# main.net
KiCad netlist of a schematic drawn in Altium Designer
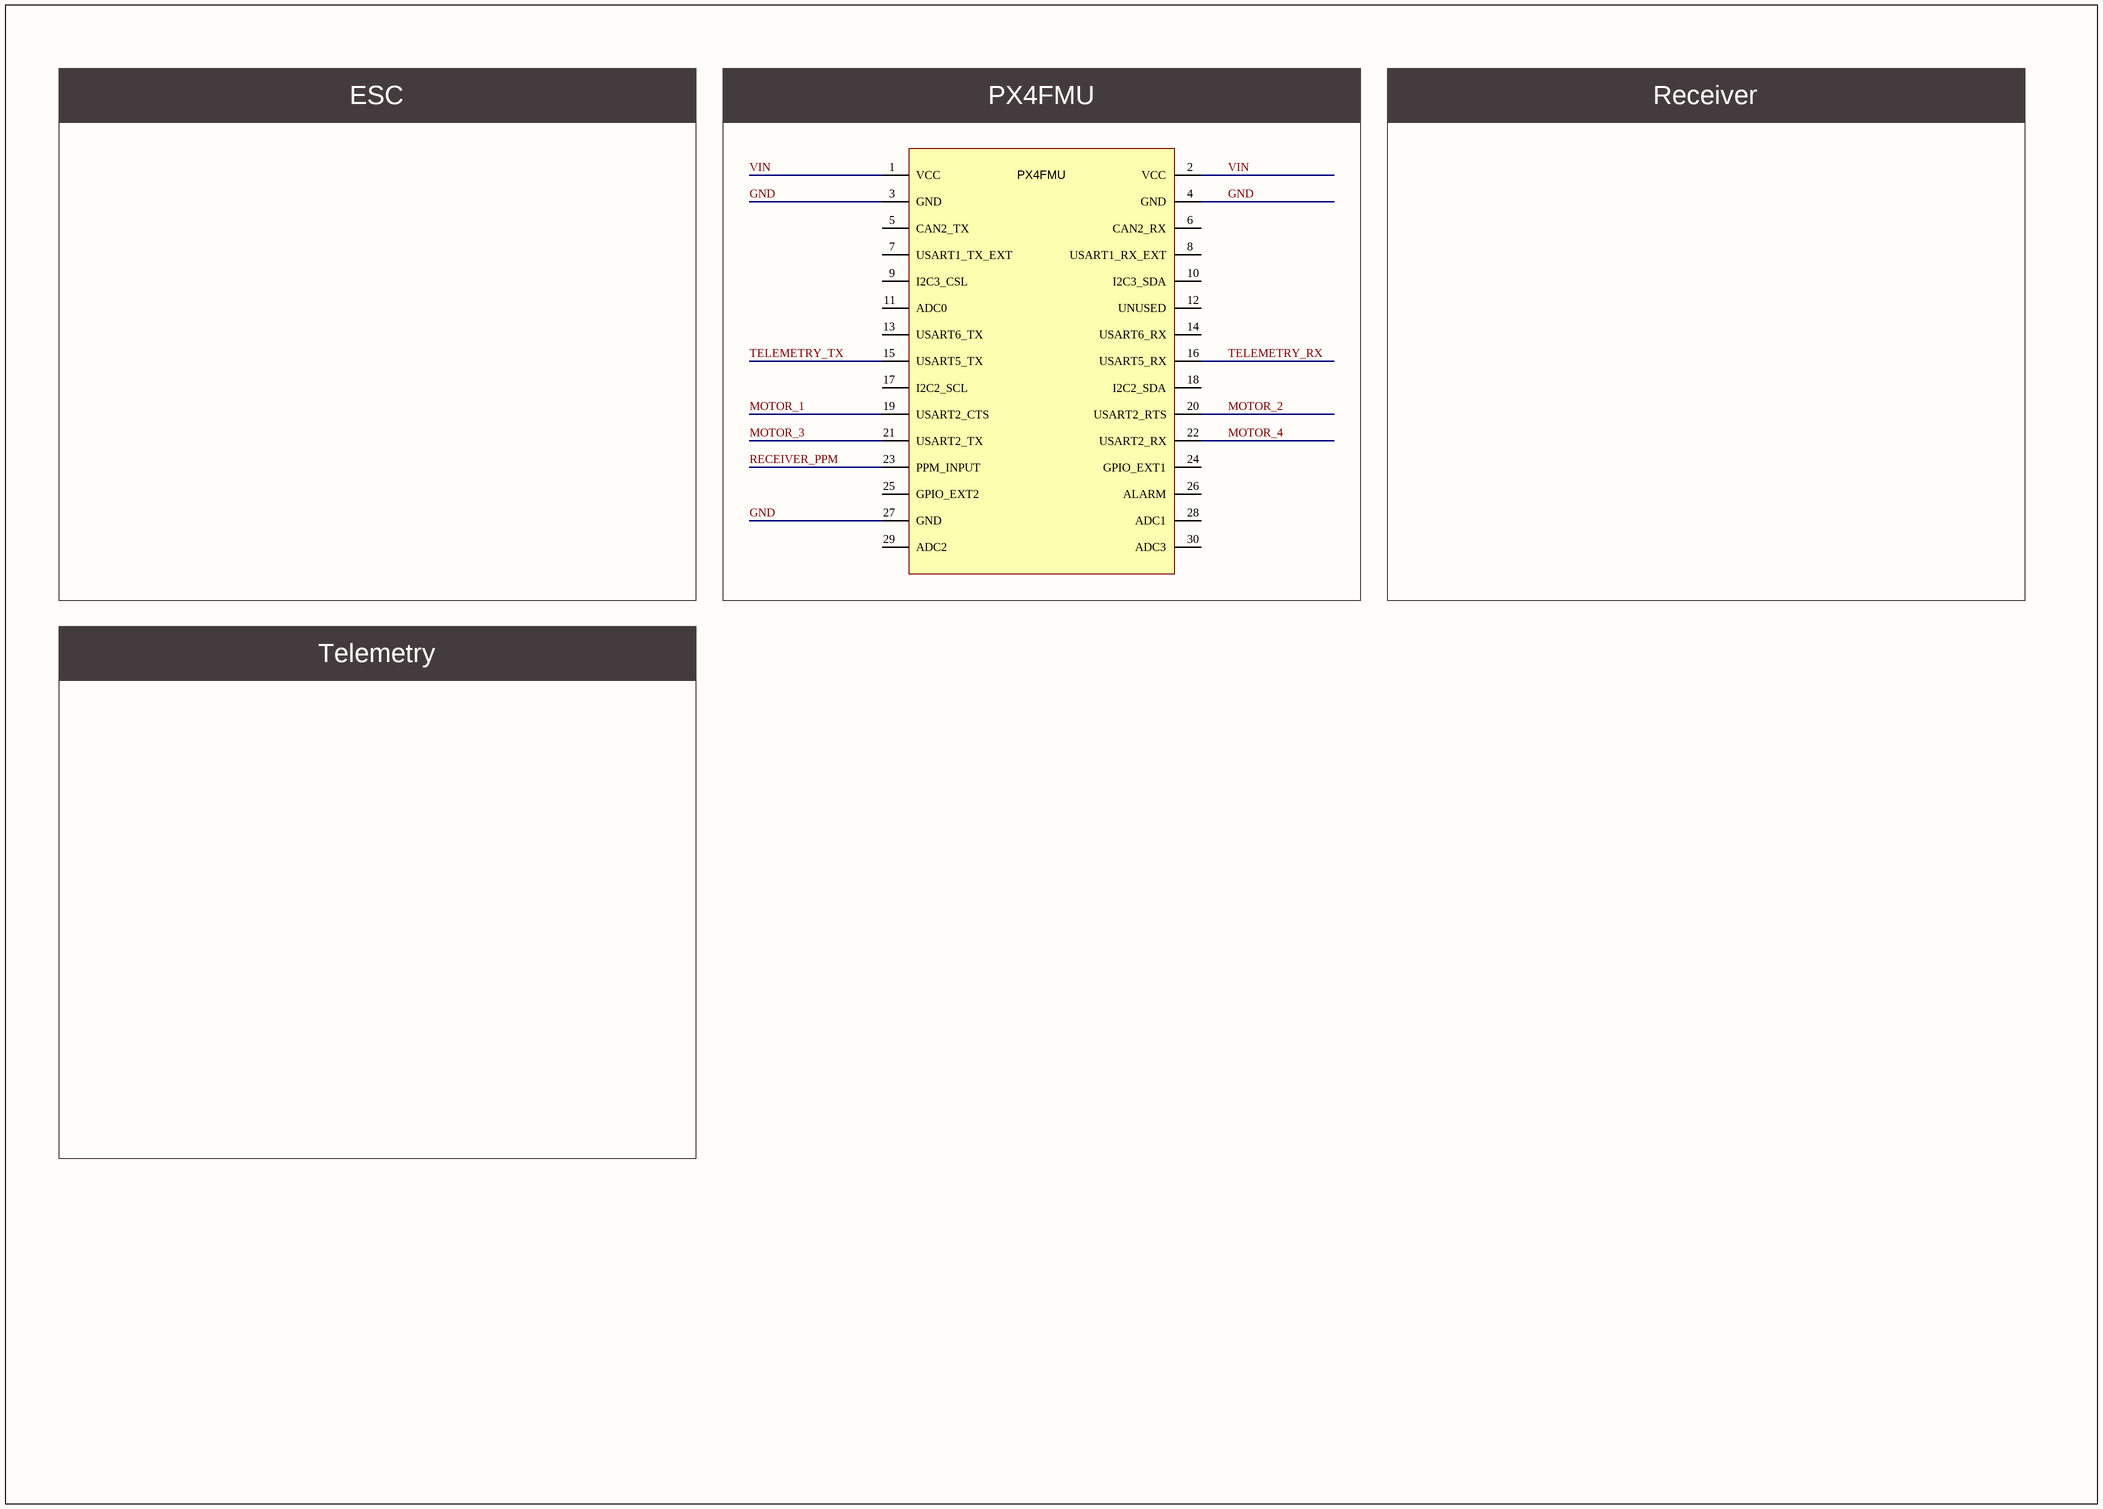
[diagram p0: main.SchDoc]

(export (version "E")
  (design (tool "Eeschema 10.0.6"))
  (components
    (comp (ref "PX4FMU")
      (value "PX4FMU")
      (description "PX4FMU flight controller")
      (libsource (lib "custom") (part "PX4FMU"))
    )
  )
  (nets
    (net (code "1") (name "/GND") (class "Default")
      (node (ref "PX4FMU") (pin "27") (pinfunction "GND_27") (pintype "passive"))
      (node (ref "PX4FMU") (pin "3") (pinfunction "GND_3") (pintype "passive"))
      (node (ref "PX4FMU") (pin "4") (pinfunction "GND_4") (pintype "passive"))
    )
    (net (code "2") (name "/MOTOR_1") (class "Default")
      (node (ref "PX4FMU") (pin "19") (pinfunction "USART2_CTS_19") (pintype "passive"))
    )
    (net (code "3") (name "/MOTOR_2") (class "Default")
      (node (ref "PX4FMU") (pin "20") (pinfunction "USART2_RTS_20") (pintype "passive"))
    )
    (net (code "4") (name "/MOTOR_3") (class "Default")
      (node (ref "PX4FMU") (pin "21") (pinfunction "USART2_TX_21") (pintype "passive"))
    )
    (net (code "5") (name "/MOTOR_4") (class "Default")
      (node (ref "PX4FMU") (pin "22") (pinfunction "USART2_RX_22") (pintype "passive"))
    )
    (net (code "6") (name "/RECEIVER_PPM") (class "Default")
      (node (ref "PX4FMU") (pin "23") (pinfunction "PPM_INPUT_23") (pintype "passive"))
    )
    (net (code "7") (name "/TELEMETRY_RX") (class "Default")
      (node (ref "PX4FMU") (pin "16") (pinfunction "USART5_RX_16") (pintype "passive"))
    )
    (net (code "8") (name "/TELEMETRY_TX") (class "Default")
      (node (ref "PX4FMU") (pin "15") (pinfunction "USART5_TX_15") (pintype "passive"))
    )
    (net (code "9") (name "/VIN") (class "Default")
      (node (ref "PX4FMU") (pin "1") (pinfunction "VCC_1") (pintype "passive"))
      (node (ref "PX4FMU") (pin "2") (pinfunction "VCC_2") (pintype "passive"))
    )
    (net (code "10") (name "unconnected-(PX4FMU-ADC0-Pad11)") (class "Default")
      (node (ref "PX4FMU") (pin "11") (pinfunction "ADC0_11") (pintype "passive"))
    )
    (net (code "11") (name "unconnected-(PX4FMU-ADC1-Pad28)") (class "Default")
      (node (ref "PX4FMU") (pin "28") (pinfunction "ADC1_28") (pintype "passive"))
    )
    (net (code "12") (name "unconnected-(PX4FMU-ADC2-Pad29)") (class "Default")
      (node (ref "PX4FMU") (pin "29") (pinfunction "ADC2_29") (pintype "passive"))
    )
    (net (code "13") (name "unconnected-(PX4FMU-ADC3-Pad30)") (class "Default")
      (node (ref "PX4FMU") (pin "30") (pinfunction "ADC3_30") (pintype "passive"))
    )
    (net (code "14") (name "unconnected-(PX4FMU-ALARM-Pad26)") (class "Default")
      (node (ref "PX4FMU") (pin "26") (pinfunction "ALARM_26") (pintype "passive"))
    )
    (net (code "15") (name "unconnected-(PX4FMU-CAN2_RX-Pad6)") (class "Default")
      (node (ref "PX4FMU") (pin "6") (pinfunction "CAN2_RX_6") (pintype "passive"))
    )
    (net (code "16") (name "unconnected-(PX4FMU-CAN2_TX-Pad5)") (class "Default")
      (node (ref "PX4FMU") (pin "5") (pinfunction "CAN2_TX_5") (pintype "passive"))
    )
    (net (code "17") (name "unconnected-(PX4FMU-GPIO_EXT1-Pad24)") (class "Default")
      (node (ref "PX4FMU") (pin "24") (pinfunction "GPIO_EXT1_24") (pintype "passive"))
    )
    (net (code "18") (name "unconnected-(PX4FMU-GPIO_EXT2-Pad25)") (class "Default")
      (node (ref "PX4FMU") (pin "25") (pinfunction "GPIO_EXT2_25") (pintype "passive"))
    )
    (net (code "19") (name "unconnected-(PX4FMU-I2C2_SCL-Pad17)") (class "Default")
      (node (ref "PX4FMU") (pin "17") (pinfunction "I2C2_SCL_17") (pintype "passive"))
    )
    (net (code "20") (name "unconnected-(PX4FMU-I2C2_SDA-Pad18)") (class "Default")
      (node (ref "PX4FMU") (pin "18") (pinfunction "I2C2_SDA_18") (pintype "passive"))
    )
    (net (code "21") (name "unconnected-(PX4FMU-I2C3_CSL-Pad9)") (class "Default")
      (node (ref "PX4FMU") (pin "9") (pinfunction "I2C3_CSL_9") (pintype "passive"))
    )
    (net (code "22") (name "unconnected-(PX4FMU-I2C3_SDA-Pad10)") (class "Default")
      (node (ref "PX4FMU") (pin "10") (pinfunction "I2C3_SDA_10") (pintype "passive"))
    )
    (net (code "23") (name "unconnected-(PX4FMU-UNUSED-Pad12)") (class "Default")
      (node (ref "PX4FMU") (pin "12") (pinfunction "UNUSED_12") (pintype "passive"))
    )
    (net (code "24") (name "unconnected-(PX4FMU-USART1_RX_EXT-Pad8)") (class "Default")
      (node (ref "PX4FMU") (pin "8") (pinfunction "USART1_RX_EXT_8") (pintype "passive"))
    )
    (net (code "25") (name "unconnected-(PX4FMU-USART1_TX_EXT-Pad7)") (class "Default")
      (node (ref "PX4FMU") (pin "7") (pinfunction "USART1_TX_EXT_7") (pintype "passive"))
    )
    (net (code "26") (name "unconnected-(PX4FMU-USART6_RX-Pad14)") (class "Default")
      (node (ref "PX4FMU") (pin "14") (pinfunction "USART6_RX_14") (pintype "passive"))
    )
    (net (code "27") (name "unconnected-(PX4FMU-USART6_TX-Pad13)") (class "Default")
      (node (ref "PX4FMU") (pin "13") (pinfunction "USART6_TX_13") (pintype "passive"))
    )
  )
)
